# Arduino_hat.net
KiCad netlist of a schematic drawn in Altium Designer
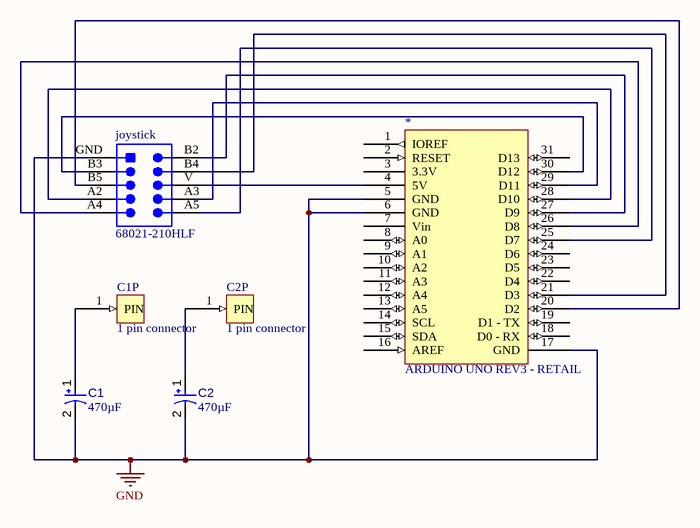
[diagram p0: Arduino_hat.SchDoc]

(export (version "E")
  (design (tool "Eeschema 10.0.6"))
  (components
    (comp (ref "*")
      (value "ARDUINO UNO REV3 - RETAIL")
      (description "Arduino Uno REV3 - Retail")
      (libsource (lib "Reykjavik University") (part "ARDUINO UNO REV3 - RETAIL-Symbol-1"))
    )
    (comp (ref "C1")
      (value "470µF")
      (footprint "CAPPR65-500-2000X1000X2200")
      (description "Aluminum Electrolytic Capacitor, 470 uF, +/- 20%, 50 V, -40 to 85 degC, 2-Pin THD, RoHS, Bulk")
      (fields (field (name "TOLERANCE") "20%") (field (name "MANUFACTURER") "Panasonic"))
      (libsource (lib "Reykjavik University") (part "CAP-P-2"))
    )
    (comp (ref "C1P")
      (value "1 pin connector")
      (libsource (lib "Reykjavik University") (part "New symbol 1"))
    )
    (comp (ref "C2")
      (value "470µF")
      (footprint "CAPPR65-500-2000X1000X2200")
      (description "Aluminum Electrolytic Capacitor, 470 uF, +/- 20%, 50 V, -40 to 85 degC, 2-Pin THD, RoHS, Bulk")
      (fields (field (name "TOLERANCE") "20%") (field (name "MANUFACTURER") "Panasonic"))
      (libsource (lib "Reykjavik University") (part "CAP-P-2"))
    )
    (comp (ref "C2P")
      (value "1 pin connector")
      (libsource (lib "Reykjavik University") (part "New symbol 1"))
    )
    (comp (ref "joystick")
      (value "68021-210HLF")
      (footprint "FCI-68021-210HLF-10_V")
      (description "Male Header, Pitch 2.54 mm, 2 x 5 Position, Height 4.83 mm, Tail Length 3.05 mm, Bulk")
      (fields (field (name "MANUFACTURER") "FCI Electronics"))
      (libsource (lib "Reykjavik University") (part "CN-2P-M-R10"))
    )
  )
  (nets
    (net (code "1") (name "GND") (class "Default")
      (node (ref "*") (pin "17") (pinfunction "GND_17") (pintype "power_in"))
      (node (ref "*") (pin "5") (pinfunction "GND_5") (pintype "power_in"))
      (node (ref "*") (pin "6") (pinfunction "GND_6") (pintype "power_in"))
      (node (ref "C1") (pin "2") (pinfunction "2_2") (pintype "passive"))
      (node (ref "C2") (pin "2") (pinfunction "2_2") (pintype "passive"))
      (node (ref "joystick") (pin "GND") (pinfunction "1_GND") (pintype "passive"))
    )
    (net (code "2") (name "Net-(*-5V)") (class "Default")
      (node (ref "*") (pin "4") (pinfunction "5V_4") (pintype "power_in"))
      (node (ref "joystick") (pin "V") (pinfunction "6_V") (pintype "passive"))
    )
    (net (code "3") (name "Net-(*-D2)") (class "Default")
      (node (ref "*") (pin "20") (pinfunction "D2_20") (pintype "bidirectional"))
      (node (ref "joystick") (pin "B5") (pinfunction "5_B5") (pintype "passive"))
    )
    (net (code "4") (name "Net-(*-D3)") (class "Default")
      (node (ref "*") (pin "21") (pinfunction "D3_21") (pintype "bidirectional"))
      (node (ref "joystick") (pin "B4") (pinfunction "4_B4") (pintype "passive"))
    )
    (net (code "5") (name "Net-(*-D7)") (class "Default")
      (node (ref "*") (pin "25") (pinfunction "D7_25") (pintype "bidirectional"))
      (node (ref "joystick") (pin "A5") (pinfunction "10_A5") (pintype "passive"))
    )
    (net (code "6") (name "Net-(*-D8)") (class "Default")
      (node (ref "*") (pin "26") (pinfunction "D8_26") (pintype "bidirectional"))
      (node (ref "joystick") (pin "A4") (pinfunction "9_A4") (pintype "passive"))
    )
    (net (code "7") (name "Net-(*-D9)") (class "Default")
      (node (ref "*") (pin "27") (pinfunction "D9_27") (pintype "bidirectional"))
      (node (ref "joystick") (pin "B2") (pinfunction "2_B2") (pintype "passive"))
    )
    (net (code "8") (name "Net-(*-D10)") (class "Default")
      (node (ref "*") (pin "28") (pinfunction "D10_28") (pintype "bidirectional"))
      (node (ref "joystick") (pin "A2") (pinfunction "7_A2") (pintype "passive"))
    )
    (net (code "9") (name "Net-(*-D11)") (class "Default")
      (node (ref "*") (pin "29") (pinfunction "D11_29") (pintype "bidirectional"))
      (node (ref "joystick") (pin "A3") (pinfunction "8_A3") (pintype "passive"))
    )
    (net (code "10") (name "Net-(*-D12)") (class "Default")
      (node (ref "*") (pin "30") (pinfunction "D12_30") (pintype "bidirectional"))
      (node (ref "joystick") (pin "B3") (pinfunction "3_B3") (pintype "passive"))
    )
    (net (code "11") (name "Net-(C1P-PIN)") (class "Default")
      (node (ref "C1") (pin "1") (pinfunction "1_1") (pintype "passive"))
      (node (ref "C1P") (pin "1") (pinfunction "PIN_1") (pintype "input"))
    )
    (net (code "12") (name "Net-(C2P-PIN)") (class "Default")
      (node (ref "C2") (pin "1") (pinfunction "1_1") (pintype "passive"))
      (node (ref "C2P") (pin "1") (pinfunction "PIN_1") (pintype "input"))
    )
    (net (code "13") (name "unconnected-(*-3.3V-Pad3)") (class "Default")
      (node (ref "*") (pin "3") (pinfunction "3.3V_3") (pintype "power_in"))
    )
    (net (code "14") (name "unconnected-(*-A0-Pad8)") (class "Default")
      (node (ref "*") (pin "8") (pinfunction "A0_8") (pintype "bidirectional"))
    )
    (net (code "15") (name "unconnected-(*-A1-Pad9)") (class "Default")
      (node (ref "*") (pin "9") (pinfunction "A1_9") (pintype "bidirectional"))
    )
    (net (code "16") (name "unconnected-(*-A2-Pad10)") (class "Default")
      (node (ref "*") (pin "10") (pinfunction "A2_10") (pintype "bidirectional"))
    )
    (net (code "17") (name "unconnected-(*-A3-Pad11)") (class "Default")
      (node (ref "*") (pin "11") (pinfunction "A3_11") (pintype "bidirectional"))
    )
    (net (code "18") (name "unconnected-(*-A4-Pad12)") (class "Default")
      (node (ref "*") (pin "12") (pinfunction "A4_12") (pintype "bidirectional"))
    )
    (net (code "19") (name "unconnected-(*-A5-Pad13)") (class "Default")
      (node (ref "*") (pin "13") (pinfunction "A5_13") (pintype "bidirectional"))
    )
    (net (code "20") (name "unconnected-(*-AREF-Pad16)") (class "Default")
      (node (ref "*") (pin "16") (pinfunction "AREF_16") (pintype "input"))
    )
    (net (code "21") (name "unconnected-(*-D0_-_RX-Pad18)") (class "Default")
      (node (ref "*") (pin "18") (pinfunction "D0_-_RX_18") (pintype "bidirectional"))
    )
    (net (code "22") (name "unconnected-(*-D1_-_TX-Pad19)") (class "Default")
      (node (ref "*") (pin "19") (pinfunction "D1_-_TX_19") (pintype "bidirectional"))
    )
    (net (code "23") (name "unconnected-(*-D4-Pad22)") (class "Default")
      (node (ref "*") (pin "22") (pinfunction "D4_22") (pintype "bidirectional"))
    )
    (net (code "24") (name "unconnected-(*-D5-Pad23)") (class "Default")
      (node (ref "*") (pin "23") (pinfunction "D5_23") (pintype "bidirectional"))
    )
    (net (code "25") (name "unconnected-(*-D6-Pad24)") (class "Default")
      (node (ref "*") (pin "24") (pinfunction "D6_24") (pintype "bidirectional"))
    )
    (net (code "26") (name "unconnected-(*-D13-Pad31)") (class "Default")
      (node (ref "*") (pin "31") (pinfunction "D13_31") (pintype "bidirectional"))
    )
    (net (code "27") (name "unconnected-(*-IOREF-Pad1)") (class "Default")
      (node (ref "*") (pin "1") (pinfunction "IOREF_1") (pintype "output"))
    )
    (net (code "28") (name "unconnected-(*-RESET-Pad2)") (class "Default")
      (node (ref "*") (pin "2") (pinfunction "RESET_2") (pintype "input"))
    )
    (net (code "29") (name "unconnected-(*-SCL-Pad14)") (class "Default")
      (node (ref "*") (pin "14") (pinfunction "SCL_14") (pintype "bidirectional"))
    )
    (net (code "30") (name "unconnected-(*-SDA-Pad15)") (class "Default")
      (node (ref "*") (pin "15") (pinfunction "SDA_15") (pintype "bidirectional"))
    )
    (net (code "31") (name "unconnected-(*-Vin-Pad7)") (class "Default")
      (node (ref "*") (pin "7") (pinfunction "Vin_7") (pintype "power_in"))
    )
  )
)
